# komahub-v1_0.net
KiCad netlist of a schematic drawn in EAGLE
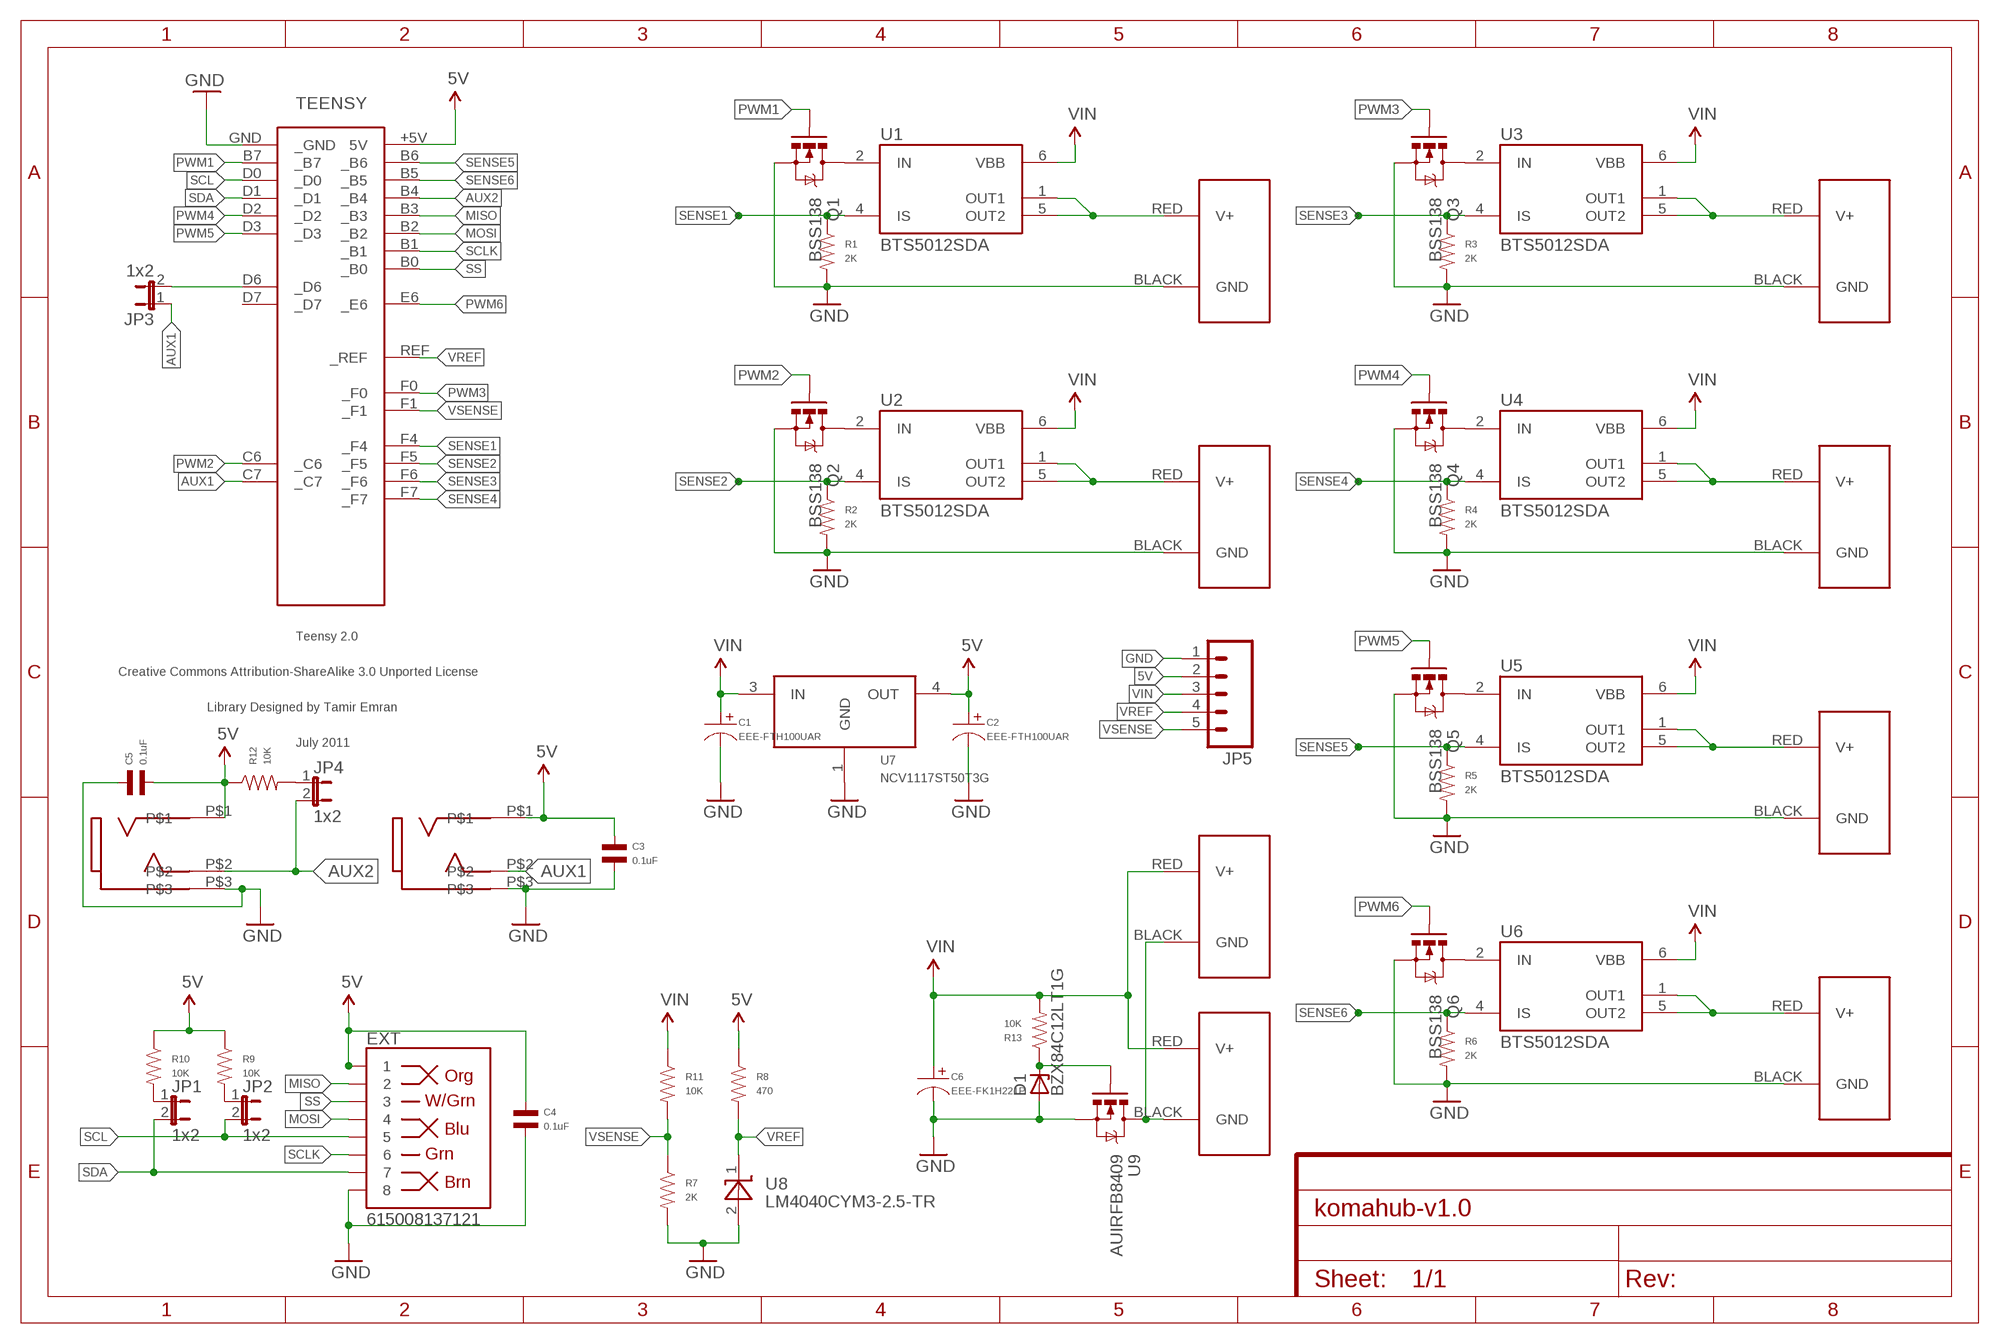
[diagram p0: schematic, sheet 1]

(export (version "E")
  (design (tool "Eeschema 10.0.6"))
  (components
    (comp (ref "AUX1")
      (value "35RASMT2BHNTRX")
      (footprint "eagle-import:35RASMT2BHNTRX")
      (libsource (lib "eagle-import") (part "35RASMT2BHNTRX"))
    )
    (comp (ref "AUX2")
      (value "35RASMT2BHNTRX")
      (footprint "eagle-import:35RASMT2BHNTRX")
      (libsource (lib "eagle-import") (part "35RASMT2BHNTRX"))
    )
    (comp (ref "C1")
      (value "EEE-FTH100UAR")
      (footprint "eagle-import:CP4MM")
      (fields (field (name "MPN") "MF-CAP-4MM-10uF"))
      (libsource (lib "eagle-import") (part "CAPACITOR_P_4MM"))
    )
    (comp (ref "C2")
      (value "EEE-FTH100UAR")
      (footprint "eagle-import:CP4MM")
      (fields (field (name "MPN") "MF-CAP-4MM-10uF"))
      (libsource (lib "eagle-import") (part "CAPACITOR_P_4MM"))
    )
    (comp (ref "C3")
      (value "0.1uF")
      (footprint "eagle-import:C0603")
      (libsource (lib "eagle-import") (part "CAPACITOR_NP_0603"))
    )
    (comp (ref "C4")
      (value "0.1uF")
      (footprint "eagle-import:C0603")
      (libsource (lib "eagle-import") (part "CAPACITOR_NP_0603"))
    )
    (comp (ref "C5")
      (value "0.1uF")
      (footprint "eagle-import:C0603")
      (libsource (lib "eagle-import") (part "CAPACITOR_NP_0603"))
    )
    (comp (ref "C6")
      (value "EEE-FK1H221P")
      (footprint "eagle-import:CP10MM")
      (fields (field (name "MPN") "EEE-FT1H221AP"))
      (libsource (lib "eagle-import") (part "CAPACITOR_P_10MM"))
    )
    (comp (ref "D1")
      (value "BZX84C12LT1G")
      (footprint "eagle-import:SOT23")
      (libsource (lib "eagle-import") (part "ZENER-DIODESOT23"))
    )
    (comp (ref "EXT")
      (value "615008137121")
      (footprint "eagle-import:RJ45-8")
      (libsource (lib "eagle-import") (part "RJ45-8PTH"))
    )
    (comp (ref "J1")
      (value "POWERPOLE_POWER25A_HORIZONTAL_G11")
      (footprint "eagle-import:POWERPOLE_PAIR_25A_HORIZ_G11")
      (libsource (lib "eagle-import") (part "POWERPOLE_POWER25A_HORIZONTAL_G11"))
    )
    (comp (ref "J2")
      (value "POWERPOLE_POWER25A_HORIZONTAL_G11")
      (footprint "eagle-import:POWERPOLE_PAIR_25A_HORIZ_G11")
      (libsource (lib "eagle-import") (part "POWERPOLE_POWER25A_HORIZONTAL_G11"))
    )
    (comp (ref "J3")
      (value "POWERPOLE_POWER25A_HORIZONTAL_G12")
      (footprint "eagle-import:POWERPOLE_PAIR_25A_HORIZ_G12")
      (libsource (lib "eagle-import") (part "POWERPOLE_POWER25A_HORIZONTAL_G12"))
    )
    (comp (ref "J4")
      (value "POWERPOLE_POWER25A_HORIZONTAL_G12")
      (footprint "eagle-import:POWERPOLE_PAIR_25A_HORIZ_G12")
      (libsource (lib "eagle-import") (part "POWERPOLE_POWER25A_HORIZONTAL_G12"))
    )
    (comp (ref "J5")
      (value "POWERPOLE_POWER25A_HORIZONTAL_G12")
      (footprint "eagle-import:POWERPOLE_PAIR_25A_HORIZ_G12")
      (libsource (lib "eagle-import") (part "POWERPOLE_POWER25A_HORIZONTAL_G12"))
    )
    (comp (ref "J6")
      (value "POWERPOLE_POWER25A_HORIZONTAL_G11")
      (footprint "eagle-import:POWERPOLE_PAIR_25A_HORIZ_G11")
      (libsource (lib "eagle-import") (part "POWERPOLE_POWER25A_HORIZONTAL_G11"))
    )
    (comp (ref "J7")
      (value "POWERPOLE_POWER25A_HORIZONTAL_G11")
      (footprint "eagle-import:POWERPOLE_PAIR_25A_HORIZ_G11")
      (libsource (lib "eagle-import") (part "POWERPOLE_POWER25A_HORIZONTAL_G11"))
    )
    (comp (ref "J9")
      (value "POWERPOLE_POWER25A_HORIZONTAL_G12")
      (footprint "eagle-import:POWERPOLE_PAIR_25A_HORIZ_G12")
      (libsource (lib "eagle-import") (part "POWERPOLE_POWER25A_HORIZONTAL_G12"))
    )
    (comp (ref "JP1")
      (value "1x2")
      (footprint "eagle-import:1X02")
      (libsource (lib "eagle-import") (part "JUMPER-2PTH"))
    )
    (comp (ref "JP2")
      (value "1x2")
      (footprint "eagle-import:1X02")
      (libsource (lib "eagle-import") (part "JUMPER-2PTH"))
    )
    (comp (ref "JP3")
      (value "1x2")
      (footprint "eagle-import:1X02")
      (libsource (lib "eagle-import") (part "JUMPER-2PTH"))
    )
    (comp (ref "JP4")
      (value "1x2")
      (footprint "eagle-import:1X02")
      (libsource (lib "eagle-import") (part "JUMPER-2PTH"))
    )
    (comp (ref "JP5")
      (value "M05PTH")
      (footprint "eagle-import:1X05")
      (libsource (lib "eagle-import") (part "M05PTH"))
    )
    (comp (ref "Q1")
      (value "BSS138")
      (footprint "eagle-import:SOT23-3")
      (libsource (lib "eagle-import") (part "MOSFET-NCHANNELAO3404A"))
    )
    (comp (ref "Q2")
      (value "BSS138")
      (footprint "eagle-import:SOT23-3")
      (libsource (lib "eagle-import") (part "MOSFET-NCHANNELAO3404A"))
    )
    (comp (ref "Q3")
      (value "BSS138")
      (footprint "eagle-import:SOT23-3")
      (libsource (lib "eagle-import") (part "MOSFET-NCHANNELAO3404A"))
    )
    (comp (ref "Q4")
      (value "BSS138")
      (footprint "eagle-import:SOT23-3")
      (libsource (lib "eagle-import") (part "MOSFET-NCHANNELAO3404A"))
    )
    (comp (ref "Q5")
      (value "BSS138")
      (footprint "eagle-import:SOT23-3")
      (libsource (lib "eagle-import") (part "MOSFET-NCHANNELAO3404A"))
    )
    (comp (ref "Q6")
      (value "BSS138")
      (footprint "eagle-import:SOT23-3")
      (libsource (lib "eagle-import") (part "MOSFET-NCHANNELAO3404A"))
    )
    (comp (ref "R1")
      (value "2K")
      (footprint "eagle-import:R0603")
      (fields (field (name "MPN") "MF-RES-0603-2K"))
      (libsource (lib "eagle-import") (part "RESISTOR_0603"))
    )
    (comp (ref "R2")
      (value "2K")
      (footprint "eagle-import:R0603")
      (fields (field (name "MPN") "MF-RES-0603-2K"))
      (libsource (lib "eagle-import") (part "RESISTOR_0603"))
    )
    (comp (ref "R3")
      (value "2K")
      (footprint "eagle-import:R0603")
      (fields (field (name "MPN") "MF-RES-0603-2K"))
      (libsource (lib "eagle-import") (part "RESISTOR_0603"))
    )
    (comp (ref "R4")
      (value "2K")
      (footprint "eagle-import:R0603")
      (fields (field (name "MPN") "MF-RES-0603-2K"))
      (libsource (lib "eagle-import") (part "RESISTOR_0603"))
    )
    (comp (ref "R5")
      (value "2K")
      (footprint "eagle-import:R0603")
      (fields (field (name "MPN") "MF-RES-0603-2K"))
      (libsource (lib "eagle-import") (part "RESISTOR_0603"))
    )
    (comp (ref "R6")
      (value "2K")
      (footprint "eagle-import:R0603")
      (fields (field (name "MPN") "MF-RES-0603-2K"))
      (libsource (lib "eagle-import") (part "RESISTOR_0603"))
    )
    (comp (ref "R7")
      (value "2K")
      (footprint "eagle-import:R0603")
      (fields (field (name "MPN") "MF-RES-0603-2K"))
      (libsource (lib "eagle-import") (part "RESISTOR_0603"))
    )
    (comp (ref "R8")
      (value "470")
      (footprint "eagle-import:R0603")
      (fields (field (name "MPN") "MF-RES-0603-470"))
      (libsource (lib "eagle-import") (part "RESISTOR_0603"))
    )
    (comp (ref "R9")
      (value "10K")
      (footprint "eagle-import:R0603")
      (fields (field (name "MPN") "MF-RES-0603-10K"))
      (libsource (lib "eagle-import") (part "RESISTOR_0603"))
    )
    (comp (ref "R10")
      (value "10K")
      (footprint "eagle-import:R0603")
      (fields (field (name "MPN") "MF-RES-0603-10K"))
      (libsource (lib "eagle-import") (part "RESISTOR_0603"))
    )
    (comp (ref "R11")
      (value "10K")
      (footprint "eagle-import:R0603")
      (fields (field (name "MPN") "MF-RES-0603-10K"))
      (libsource (lib "eagle-import") (part "RESISTOR_0603"))
    )
    (comp (ref "R12")
      (value "10K")
      (footprint "eagle-import:R0603")
      (fields (field (name "MPN") "MF-RES-0603-10K"))
      (libsource (lib "eagle-import") (part "RESISTOR_0603"))
    )
    (comp (ref "R13")
      (value "10K")
      (footprint "eagle-import:R0603")
      (fields (field (name "MPN") "MF-RES-0603-10K"))
      (libsource (lib "eagle-import") (part "RESISTOR_0603"))
    )
    (comp (ref "TEENSY")
      (value "TEENSY-SIMPLE")
      (footprint "eagle-import:TEENSY-SIMPLE")
      (libsource (lib "eagle-import") (part "TEENSY-SIMPLE"))
    )
    (comp (ref "U1")
      (value "BTS5012SDA")
      (footprint "eagle-import:TO114P998X235-5_6N")
      (libsource (lib "eagle-import") (part "BTS5016SDA"))
    )
    (comp (ref "U2")
      (value "BTS5012SDA")
      (footprint "eagle-import:TO114P998X235-5_6N")
      (libsource (lib "eagle-import") (part "BTS5016SDA"))
    )
    (comp (ref "U3")
      (value "BTS5012SDA")
      (footprint "eagle-import:TO114P998X235-5_6N")
      (libsource (lib "eagle-import") (part "BTS5016SDA"))
    )
    (comp (ref "U4")
      (value "BTS5012SDA")
      (footprint "eagle-import:TO114P998X235-5_6N")
      (libsource (lib "eagle-import") (part "BTS5016SDA"))
    )
    (comp (ref "U5")
      (value "BTS5012SDA")
      (footprint "eagle-import:TO114P998X235-5_6N")
      (libsource (lib "eagle-import") (part "BTS5016SDA"))
    )
    (comp (ref "U6")
      (value "BTS5012SDA")
      (footprint "eagle-import:TO114P998X235-5_6N")
      (libsource (lib "eagle-import") (part "BTS5016SDA"))
    )
    (comp (ref "U7")
      (value "NCV1117ST50T3G")
      (footprint "eagle-import:DPAK")
      (libsource (lib "eagle-import") (part "NCV1117"))
    )
    (comp (ref "U8")
      (value "LM4040CYM3-2.5-TR")
      (footprint "eagle-import:SOT-23")
      (libsource (lib "eagle-import") (part "LM4040CYM3-2.5"))
    )
    (comp (ref "U9")
      (value "AUIRFB8409")
      (footprint "eagle-import:TO220AV")
      (libsource (lib "eagle-import") (part "AUIRFB8409"))
    )
  )
  (nets
    (net (code "1") (name "5V") (class "Default")
      (node (ref "AUX1") (pin "P$1") (pinfunction "P$1_P$1") (pintype "bidirectional"))
      (node (ref "AUX2") (pin "P$1") (pinfunction "P$1_P$1") (pintype "bidirectional"))
      (node (ref "C2") (pin "P$1") (pinfunction "P$1_P$1") (pintype "passive"))
      (node (ref "C3") (pin "P$1") (pinfunction "P$1_P$1") (pintype "passive"))
      (node (ref "C4") (pin "P$1") (pinfunction "P$1_P$1") (pintype "passive"))
      (node (ref "C5") (pin "P$2") (pinfunction "P$2_P$2") (pintype "passive"))
      (node (ref "EXT") (pin "1") (pinfunction "1_1") (pintype "bidirectional"))
      (node (ref "JP5") (pin "2") (pinfunction "2_2") (pintype "passive"))
      (node (ref "R10") (pin "P$1") (pinfunction "P$1_P$1") (pintype "passive"))
      (node (ref "R12") (pin "P$1") (pinfunction "P$1_P$1") (pintype "passive"))
      (node (ref "R8") (pin "P$1") (pinfunction "P$1_P$1") (pintype "passive"))
      (node (ref "R9") (pin "P$1") (pinfunction "P$1_P$1") (pintype "passive"))
      (node (ref "TEENSY") (pin "+5V") (pinfunction "5V_+5V") (pintype "bidirectional"))
      (node (ref "U7") (pin "4") (pinfunction "OUT_4") (pintype "bidirectional"))
    )
    (net (code "2") (name "AUX1") (class "Default")
      (node (ref "AUX1") (pin "P$2") (pinfunction "P$2_P$2") (pintype "bidirectional"))
      (node (ref "JP3") (pin "1") (pinfunction "1_1") (pintype "passive"))
      (node (ref "TEENSY") (pin "C7") (pinfunction "_C7_C7") (pintype "bidirectional"))
    )
    (net (code "3") (name "AUX2") (class "Default")
      (node (ref "AUX2") (pin "P$2") (pinfunction "P$2_P$2") (pintype "bidirectional"))
      (node (ref "JP4") (pin "2") (pinfunction "2_2") (pintype "passive"))
      (node (ref "TEENSY") (pin "B4") (pinfunction "_B4_B4") (pintype "bidirectional"))
    )
    (net (code "4") (name "GND") (class "Default")
      (node (ref "AUX1") (pin "P$3") (pinfunction "P$3_P$3") (pintype "bidirectional"))
      (node (ref "AUX2") (pin "P$3") (pinfunction "P$3_P$3") (pintype "bidirectional"))
      (node (ref "C1") (pin "P$2") (pinfunction "P$2_P$2") (pintype "passive"))
      (node (ref "C2") (pin "P$2") (pinfunction "P$2_P$2") (pintype "passive"))
      (node (ref "C3") (pin "P$2") (pinfunction "P$2_P$2") (pintype "passive"))
      (node (ref "C4") (pin "P$2") (pinfunction "P$2_P$2") (pintype "passive"))
      (node (ref "C5") (pin "P$1") (pinfunction "P$1_P$1") (pintype "passive"))
      (node (ref "C6") (pin "P$2") (pinfunction "P$2_P$2") (pintype "passive"))
      (node (ref "D1") (pin "1") (pinfunction "A_1") (pintype "passive"))
      (node (ref "EXT") (pin "8") (pinfunction "8_8") (pintype "bidirectional"))
      (node (ref "J1") (pin "BLACK") (pinfunction "GND_BLACK") (pintype "power_in"))
      (node (ref "J2") (pin "BLACK") (pinfunction "GND_BLACK") (pintype "power_in"))
      (node (ref "J3") (pin "BLACK") (pinfunction "GND_BLACK") (pintype "power_in"))
      (node (ref "J5") (pin "BLACK") (pinfunction "GND_BLACK") (pintype "power_in"))
      (node (ref "J7") (pin "BLACK") (pinfunction "GND_BLACK") (pintype "power_in"))
      (node (ref "J9") (pin "BLACK") (pinfunction "GND_BLACK") (pintype "power_in"))
      (node (ref "JP5") (pin "1") (pinfunction "1_1") (pintype "passive"))
      (node (ref "Q1") (pin "2") (pinfunction "S_2") (pintype "passive"))
      (node (ref "Q2") (pin "2") (pinfunction "S_2") (pintype "passive"))
      (node (ref "Q3") (pin "2") (pinfunction "S_2") (pintype "passive"))
      (node (ref "Q4") (pin "2") (pinfunction "S_2") (pintype "passive"))
      (node (ref "Q5") (pin "2") (pinfunction "S_2") (pintype "passive"))
      (node (ref "Q6") (pin "2") (pinfunction "S_2") (pintype "passive"))
      (node (ref "R1") (pin "P$2") (pinfunction "P$2_P$2") (pintype "passive"))
      (node (ref "R2") (pin "P$2") (pinfunction "P$2_P$2") (pintype "passive"))
      (node (ref "R3") (pin "P$2") (pinfunction "P$2_P$2") (pintype "passive"))
      (node (ref "R4") (pin "P$2") (pinfunction "P$2_P$2") (pintype "passive"))
      (node (ref "R5") (pin "P$2") (pinfunction "P$2_P$2") (pintype "passive"))
      (node (ref "R6") (pin "P$2") (pinfunction "P$2_P$2") (pintype "passive"))
      (node (ref "R7") (pin "P$2") (pinfunction "P$2_P$2") (pintype "passive"))
      (node (ref "TEENSY") (pin "GND") (pinfunction "_GND_GND") (pintype "bidirectional"))
      (node (ref "U7") (pin "1") (pinfunction "GND_1") (pintype "bidirectional"))
      (node (ref "U8") (pin "2") (pinfunction "A_2") (pintype "output"))
      (node (ref "U9") (pin "3") (pinfunction "S_3") (pintype "passive"))
    )
    (net (code "5") (name "MISO") (class "Default")
      (node (ref "EXT") (pin "2") (pinfunction "2_2") (pintype "bidirectional"))
      (node (ref "TEENSY") (pin "B3") (pinfunction "_B3_B3") (pintype "bidirectional"))
    )
    (net (code "6") (name "MOSI") (class "Default")
      (node (ref "EXT") (pin "4") (pinfunction "4_4") (pintype "bidirectional"))
      (node (ref "TEENSY") (pin "B2") (pinfunction "_B2_B2") (pintype "bidirectional"))
    )
    (net (code "7") (name "Net-(D1-C)") (class "Default")
      (node (ref "D1") (pin "3") (pinfunction "C_3") (pintype "passive"))
      (node (ref "R13") (pin "P$1") (pinfunction "P$1_P$1") (pintype "passive"))
      (node (ref "U9") (pin "1") (pinfunction "G_1") (pintype "passive"))
    )
    (net (code "8") (name "Net-(J1-V+)") (class "Default")
      (node (ref "J1") (pin "RED") (pinfunction "V+_RED") (pintype "power_in"))
      (node (ref "U3") (pin "1") (pinfunction "OUT1_1") (pintype "output"))
      (node (ref "U3") (pin "5") (pinfunction "OUT2_5") (pintype "output"))
    )
    (net (code "9") (name "Net-(J2-V+)") (class "Default")
      (node (ref "J2") (pin "RED") (pinfunction "V+_RED") (pintype "power_in"))
      (node (ref "U1") (pin "1") (pinfunction "OUT1_1") (pintype "output"))
      (node (ref "U1") (pin "5") (pinfunction "OUT2_5") (pintype "output"))
    )
    (net (code "10") (name "Net-(J3-V+)") (class "Default")
      (node (ref "J3") (pin "RED") (pinfunction "V+_RED") (pintype "power_in"))
      (node (ref "U2") (pin "1") (pinfunction "OUT1_1") (pintype "output"))
      (node (ref "U2") (pin "5") (pinfunction "OUT2_5") (pintype "output"))
    )
    (net (code "11") (name "Net-(J4-GND)") (class "Default")
      (node (ref "J4") (pin "BLACK") (pinfunction "GND_BLACK") (pintype "power_in"))
      (node (ref "J6") (pin "BLACK") (pinfunction "GND_BLACK") (pintype "power_in"))
      (node (ref "U9") (pin "2") (pinfunction "D_2") (pintype "passive"))
    )
    (net (code "12") (name "Net-(J5-V+)") (class "Default")
      (node (ref "J5") (pin "RED") (pinfunction "V+_RED") (pintype "power_in"))
      (node (ref "U4") (pin "1") (pinfunction "OUT1_1") (pintype "output"))
      (node (ref "U4") (pin "5") (pinfunction "OUT2_5") (pintype "output"))
    )
    (net (code "13") (name "Net-(J7-V+)") (class "Default")
      (node (ref "J7") (pin "RED") (pinfunction "V+_RED") (pintype "power_in"))
      (node (ref "U5") (pin "1") (pinfunction "OUT1_1") (pintype "output"))
      (node (ref "U5") (pin "5") (pinfunction "OUT2_5") (pintype "output"))
    )
    (net (code "14") (name "Net-(J9-V+)") (class "Default")
      (node (ref "J9") (pin "RED") (pinfunction "V+_RED") (pintype "power_in"))
      (node (ref "U6") (pin "1") (pinfunction "OUT1_1") (pintype "output"))
      (node (ref "U6") (pin "5") (pinfunction "OUT2_5") (pintype "output"))
    )
    (net (code "15") (name "Net-(JP1-Pad1)") (class "Default")
      (node (ref "JP1") (pin "1") (pinfunction "1_1") (pintype "passive"))
      (node (ref "R10") (pin "P$2") (pinfunction "P$2_P$2") (pintype "passive"))
    )
    (net (code "16") (name "Net-(JP2-Pad1)") (class "Default")
      (node (ref "JP2") (pin "1") (pinfunction "1_1") (pintype "passive"))
      (node (ref "R9") (pin "P$2") (pinfunction "P$2_P$2") (pintype "passive"))
    )
    (net (code "17") (name "Net-(JP4-Pad1)") (class "Default")
      (node (ref "JP4") (pin "1") (pinfunction "1_1") (pintype "passive"))
      (node (ref "R12") (pin "P$2") (pinfunction "P$2_P$2") (pintype "passive"))
    )
    (net (code "18") (name "Net-(Q1-D)") (class "Default")
      (node (ref "Q1") (pin "3") (pinfunction "D_3") (pintype "passive"))
      (node (ref "U1") (pin "2") (pinfunction "IN_2") (pintype "input"))
    )
    (net (code "19") (name "Net-(Q2-D)") (class "Default")
      (node (ref "Q2") (pin "3") (pinfunction "D_3") (pintype "passive"))
      (node (ref "U2") (pin "2") (pinfunction "IN_2") (pintype "input"))
    )
    (net (code "20") (name "Net-(Q3-D)") (class "Default")
      (node (ref "Q3") (pin "3") (pinfunction "D_3") (pintype "passive"))
      (node (ref "U3") (pin "2") (pinfunction "IN_2") (pintype "input"))
    )
    (net (code "21") (name "Net-(Q4-D)") (class "Default")
      (node (ref "Q4") (pin "3") (pinfunction "D_3") (pintype "passive"))
      (node (ref "U4") (pin "2") (pinfunction "IN_2") (pintype "input"))
    )
    (net (code "22") (name "Net-(Q5-D)") (class "Default")
      (node (ref "Q5") (pin "3") (pinfunction "D_3") (pintype "passive"))
      (node (ref "U5") (pin "2") (pinfunction "IN_2") (pintype "input"))
    )
    (net (code "23") (name "Net-(Q6-D)") (class "Default")
      (node (ref "Q6") (pin "3") (pinfunction "D_3") (pintype "passive"))
      (node (ref "U6") (pin "2") (pinfunction "IN_2") (pintype "input"))
    )
    (net (code "24") (name "Net-(TEENSY-_D6)") (class "Default")
      (node (ref "JP3") (pin "2") (pinfunction "2_2") (pintype "passive"))
      (node (ref "TEENSY") (pin "D6") (pinfunction "_D6_D6") (pintype "bidirectional"))
    )
    (net (code "25") (name "PWM1") (class "Default")
      (node (ref "Q1") (pin "1") (pinfunction "G_1") (pintype "passive"))
      (node (ref "TEENSY") (pin "B7") (pinfunction "_B7_B7") (pintype "bidirectional"))
    )
    (net (code "26") (name "PWM2") (class "Default")
      (node (ref "Q2") (pin "1") (pinfunction "G_1") (pintype "passive"))
      (node (ref "TEENSY") (pin "C6") (pinfunction "_C6_C6") (pintype "bidirectional"))
    )
    (net (code "27") (name "PWM3") (class "Default")
      (node (ref "Q3") (pin "1") (pinfunction "G_1") (pintype "passive"))
      (node (ref "TEENSY") (pin "F0") (pinfunction "_F0_F0") (pintype "bidirectional"))
    )
    (net (code "28") (name "PWM4") (class "Default")
      (node (ref "Q4") (pin "1") (pinfunction "G_1") (pintype "passive"))
      (node (ref "TEENSY") (pin "D2") (pinfunction "_D2_D2") (pintype "bidirectional"))
    )
    (net (code "29") (name "PWM5") (class "Default")
      (node (ref "Q5") (pin "1") (pinfunction "G_1") (pintype "passive"))
      (node (ref "TEENSY") (pin "D3") (pinfunction "_D3_D3") (pintype "bidirectional"))
    )
    (net (code "30") (name "PWM6") (class "Default")
      (node (ref "Q6") (pin "1") (pinfunction "G_1") (pintype "passive"))
      (node (ref "TEENSY") (pin "E6") (pinfunction "_E6_E6") (pintype "bidirectional"))
    )
    (net (code "31") (name "SCL") (class "Default")
      (node (ref "EXT") (pin "5") (pinfunction "5_5") (pintype "bidirectional"))
      (node (ref "JP2") (pin "2") (pinfunction "2_2") (pintype "passive"))
      (node (ref "TEENSY") (pin "D0") (pinfunction "_D0_D0") (pintype "bidirectional"))
    )
    (net (code "32") (name "SCLK") (class "Default")
      (node (ref "EXT") (pin "6") (pinfunction "6_6") (pintype "bidirectional"))
      (node (ref "TEENSY") (pin "B1") (pinfunction "_B1_B1") (pintype "bidirectional"))
    )
    (net (code "33") (name "SDA") (class "Default")
      (node (ref "EXT") (pin "7") (pinfunction "7_7") (pintype "bidirectional"))
      (node (ref "JP1") (pin "2") (pinfunction "2_2") (pintype "passive"))
      (node (ref "TEENSY") (pin "D1") (pinfunction "_D1_D1") (pintype "bidirectional"))
    )
    (net (code "34") (name "SENSE1") (class "Default")
      (node (ref "R1") (pin "P$1") (pinfunction "P$1_P$1") (pintype "passive"))
      (node (ref "TEENSY") (pin "F4") (pinfunction "_F4_F4") (pintype "bidirectional"))
      (node (ref "U1") (pin "4") (pinfunction "IS_4") (pintype "output"))
    )
    (net (code "35") (name "SENSE2") (class "Default")
      (node (ref "R2") (pin "P$1") (pinfunction "P$1_P$1") (pintype "passive"))
      (node (ref "TEENSY") (pin "F5") (pinfunction "_F5_F5") (pintype "bidirectional"))
      (node (ref "U2") (pin "4") (pinfunction "IS_4") (pintype "output"))
    )
    (net (code "36") (name "SENSE3") (class "Default")
      (node (ref "R3") (pin "P$1") (pinfunction "P$1_P$1") (pintype "passive"))
      (node (ref "TEENSY") (pin "F6") (pinfunction "_F6_F6") (pintype "bidirectional"))
      (node (ref "U3") (pin "4") (pinfunction "IS_4") (pintype "output"))
    )
    (net (code "37") (name "SENSE4") (class "Default")
      (node (ref "R4") (pin "P$1") (pinfunction "P$1_P$1") (pintype "passive"))
      (node (ref "TEENSY") (pin "F7") (pinfunction "_F7_F7") (pintype "bidirectional"))
      (node (ref "U4") (pin "4") (pinfunction "IS_4") (pintype "output"))
    )
    (net (code "38") (name "SENSE5") (class "Default")
      (node (ref "R5") (pin "P$1") (pinfunction "P$1_P$1") (pintype "passive"))
      (node (ref "TEENSY") (pin "B6") (pinfunction "_B6_B6") (pintype "bidirectional"))
      (node (ref "U5") (pin "4") (pinfunction "IS_4") (pintype "output"))
    )
    (net (code "39") (name "SENSE6") (class "Default")
      (node (ref "R6") (pin "P$1") (pinfunction "P$1_P$1") (pintype "passive"))
      (node (ref "TEENSY") (pin "B5") (pinfunction "_B5_B5") (pintype "bidirectional"))
      (node (ref "U6") (pin "4") (pinfunction "IS_4") (pintype "output"))
    )
    (net (code "40") (name "SS") (class "Default")
      (node (ref "EXT") (pin "3") (pinfunction "3_3") (pintype "bidirectional"))
      (node (ref "TEENSY") (pin "B0") (pinfunction "_B0_B0") (pintype "bidirectional"))
    )
    (net (code "41") (name "VIN") (class "Default")
      (node (ref "C1") (pin "P$1") (pinfunction "P$1_P$1") (pintype "passive"))
      (node (ref "C6") (pin "P$1") (pinfunction "P$1_P$1") (pintype "passive"))
      (node (ref "J4") (pin "RED") (pinfunction "V+_RED") (pintype "power_in"))
      (node (ref "J6") (pin "RED") (pinfunction "V+_RED") (pintype "power_in"))
      (node (ref "JP5") (pin "3") (pinfunction "3_3") (pintype "passive"))
      (node (ref "R11") (pin "P$1") (pinfunction "P$1_P$1") (pintype "passive"))
      (node (ref "R13") (pin "P$2") (pinfunction "P$2_P$2") (pintype "passive"))
      (node (ref "U1") (pin "6") (pinfunction "VBB_6") (pintype "power_in"))
      (node (ref "U2") (pin "6") (pinfunction "VBB_6") (pintype "power_in"))
      (node (ref "U3") (pin "6") (pinfunction "VBB_6") (pintype "power_in"))
      (node (ref "U4") (pin "6") (pinfunction "VBB_6") (pintype "power_in"))
      (node (ref "U5") (pin "6") (pinfunction "VBB_6") (pintype "power_in"))
      (node (ref "U6") (pin "6") (pinfunction "VBB_6") (pintype "power_in"))
      (node (ref "U7") (pin "3") (pinfunction "IN_3") (pintype "bidirectional"))
    )
    (net (code "42") (name "VREF") (class "Default")
      (node (ref "JP5") (pin "4") (pinfunction "4_4") (pintype "passive"))
      (node (ref "R8") (pin "P$2") (pinfunction "P$2_P$2") (pintype "passive"))
      (node (ref "TEENSY") (pin "REF") (pinfunction "_REF_REF") (pintype "bidirectional"))
      (node (ref "U8") (pin "1") (pinfunction "C_1") (pintype "input"))
    )
    (net (code "43") (name "VSENSE") (class "Default")
      (node (ref "JP5") (pin "5") (pinfunction "5_5") (pintype "passive"))
      (node (ref "R11") (pin "P$2") (pinfunction "P$2_P$2") (pintype "passive"))
      (node (ref "R7") (pin "P$1") (pinfunction "P$1_P$1") (pintype "passive"))
      (node (ref "TEENSY") (pin "F1") (pinfunction "_F1_F1") (pintype "bidirectional"))
    )
    (net (code "44") (name "unconnected-(TEENSY-_D7-PadD7)") (class "Default")
      (node (ref "TEENSY") (pin "D7") (pinfunction "_D7_D7") (pintype "bidirectional"))
    )
  )
)
